# interfaces.net
KiCad netlist of a schematic drawn in EAGLE
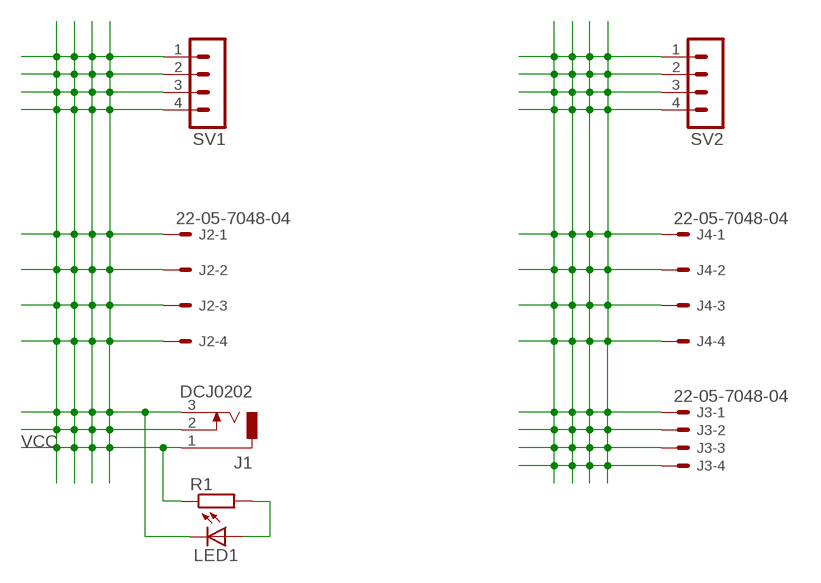
[diagram p0: schematic, sheet 1]

(export (version "E")
  (design (tool "Eeschema 10.0.6"))
  (components
    (comp (ref "J1")
      (value "DCJ0202")
      (footprint "eagle-import:DCJ0202")
      (libsource (lib "eagle-import") (part "DCJ0202"))
    )
    (comp (ref "J2")
      (value "22-05-7048-04")
      (footprint "eagle-import:7395-04")
      (libsource (lib "eagle-import") (part "22-?-0405-7048"))
    )
    (comp (ref "J3")
      (value "22-05-7048-04")
      (footprint "eagle-import:7395-04")
      (libsource (lib "eagle-import") (part "22-?-0405-7048"))
    )
    (comp (ref "J4")
      (value "22-05-7048-04")
      (footprint "eagle-import:7395-04")
      (libsource (lib "eagle-import") (part "22-?-0405-7048"))
    )
    (comp (ref "LED1")
      (value "LEDSML0805")
      (footprint "eagle-import:SML0805")
      (libsource (lib "eagle-import") (part "LEDSML0805"))
    )
    (comp (ref "R1")
      (value "R-EU_R0805")
      (footprint "eagle-import:R0805")
      (libsource (lib "eagle-import") (part "R-EU_R0805"))
    )
    (comp (ref "SV1")
      (value "MA04-1")
      (footprint "eagle-import:MA04-1")
      (libsource (lib "eagle-import") (part "MA04-1"))
    )
    (comp (ref "SV2")
      (value "MA04-1")
      (footprint "eagle-import:MA04-1")
      (libsource (lib "eagle-import") (part "MA04-1"))
    )
  )
  (nets
    (net (code "1") (name "/VCC") (class "Default")
      (node (ref "J1") (pin "1") (pinfunction "1_1") (pintype "passive"))
      (node (ref "J1") (pin "2") (pinfunction "2_2") (pintype "passive"))
      (node (ref "J1") (pin "3") (pinfunction "3_3") (pintype "passive"))
      (node (ref "J2") (pin "1") (pinfunction "S_1") (pintype "passive"))
      (node (ref "J2") (pin "2") (pinfunction "S_2") (pintype "passive"))
      (node (ref "J2") (pin "3") (pinfunction "S_3") (pintype "passive"))
      (node (ref "J2") (pin "4") (pinfunction "S_4") (pintype "passive"))
      (node (ref "LED1") (pin "C") (pinfunction "C_C") (pintype "passive"))
      (node (ref "R1") (pin "1") (pinfunction "1_1") (pintype "passive"))
      (node (ref "SV1") (pin "1") (pinfunction "1_1") (pintype "passive"))
      (node (ref "SV1") (pin "2") (pinfunction "2_2") (pintype "passive"))
      (node (ref "SV1") (pin "3") (pinfunction "3_3") (pintype "passive"))
      (node (ref "SV1") (pin "4") (pinfunction "4_4") (pintype "passive"))
    )
    (net (code "2") (name "Net-(J3A-S)") (class "Default")
      (node (ref "J3") (pin "1") (pinfunction "S_1") (pintype "passive"))
      (node (ref "J3") (pin "2") (pinfunction "S_2") (pintype "passive"))
      (node (ref "J3") (pin "3") (pinfunction "S_3") (pintype "passive"))
      (node (ref "J3") (pin "4") (pinfunction "S_4") (pintype "passive"))
      (node (ref "J4") (pin "1") (pinfunction "S_1") (pintype "passive"))
      (node (ref "J4") (pin "2") (pinfunction "S_2") (pintype "passive"))
      (node (ref "J4") (pin "3") (pinfunction "S_3") (pintype "passive"))
      (node (ref "J4") (pin "4") (pinfunction "S_4") (pintype "passive"))
      (node (ref "SV2") (pin "1") (pinfunction "1_1") (pintype "passive"))
      (node (ref "SV2") (pin "2") (pinfunction "2_2") (pintype "passive"))
      (node (ref "SV2") (pin "3") (pinfunction "3_3") (pintype "passive"))
      (node (ref "SV2") (pin "4") (pinfunction "4_4") (pintype "passive"))
    )
    (net (code "3") (name "Net-(LED1-PadA)") (class "Default")
      (node (ref "LED1") (pin "A") (pinfunction "A_A") (pintype "passive"))
      (node (ref "R1") (pin "2") (pinfunction "2_2") (pintype "passive"))
    )
  )
)
